# circuit_R2a.net
KiCad netlist of a schematic drawn in EAGLE
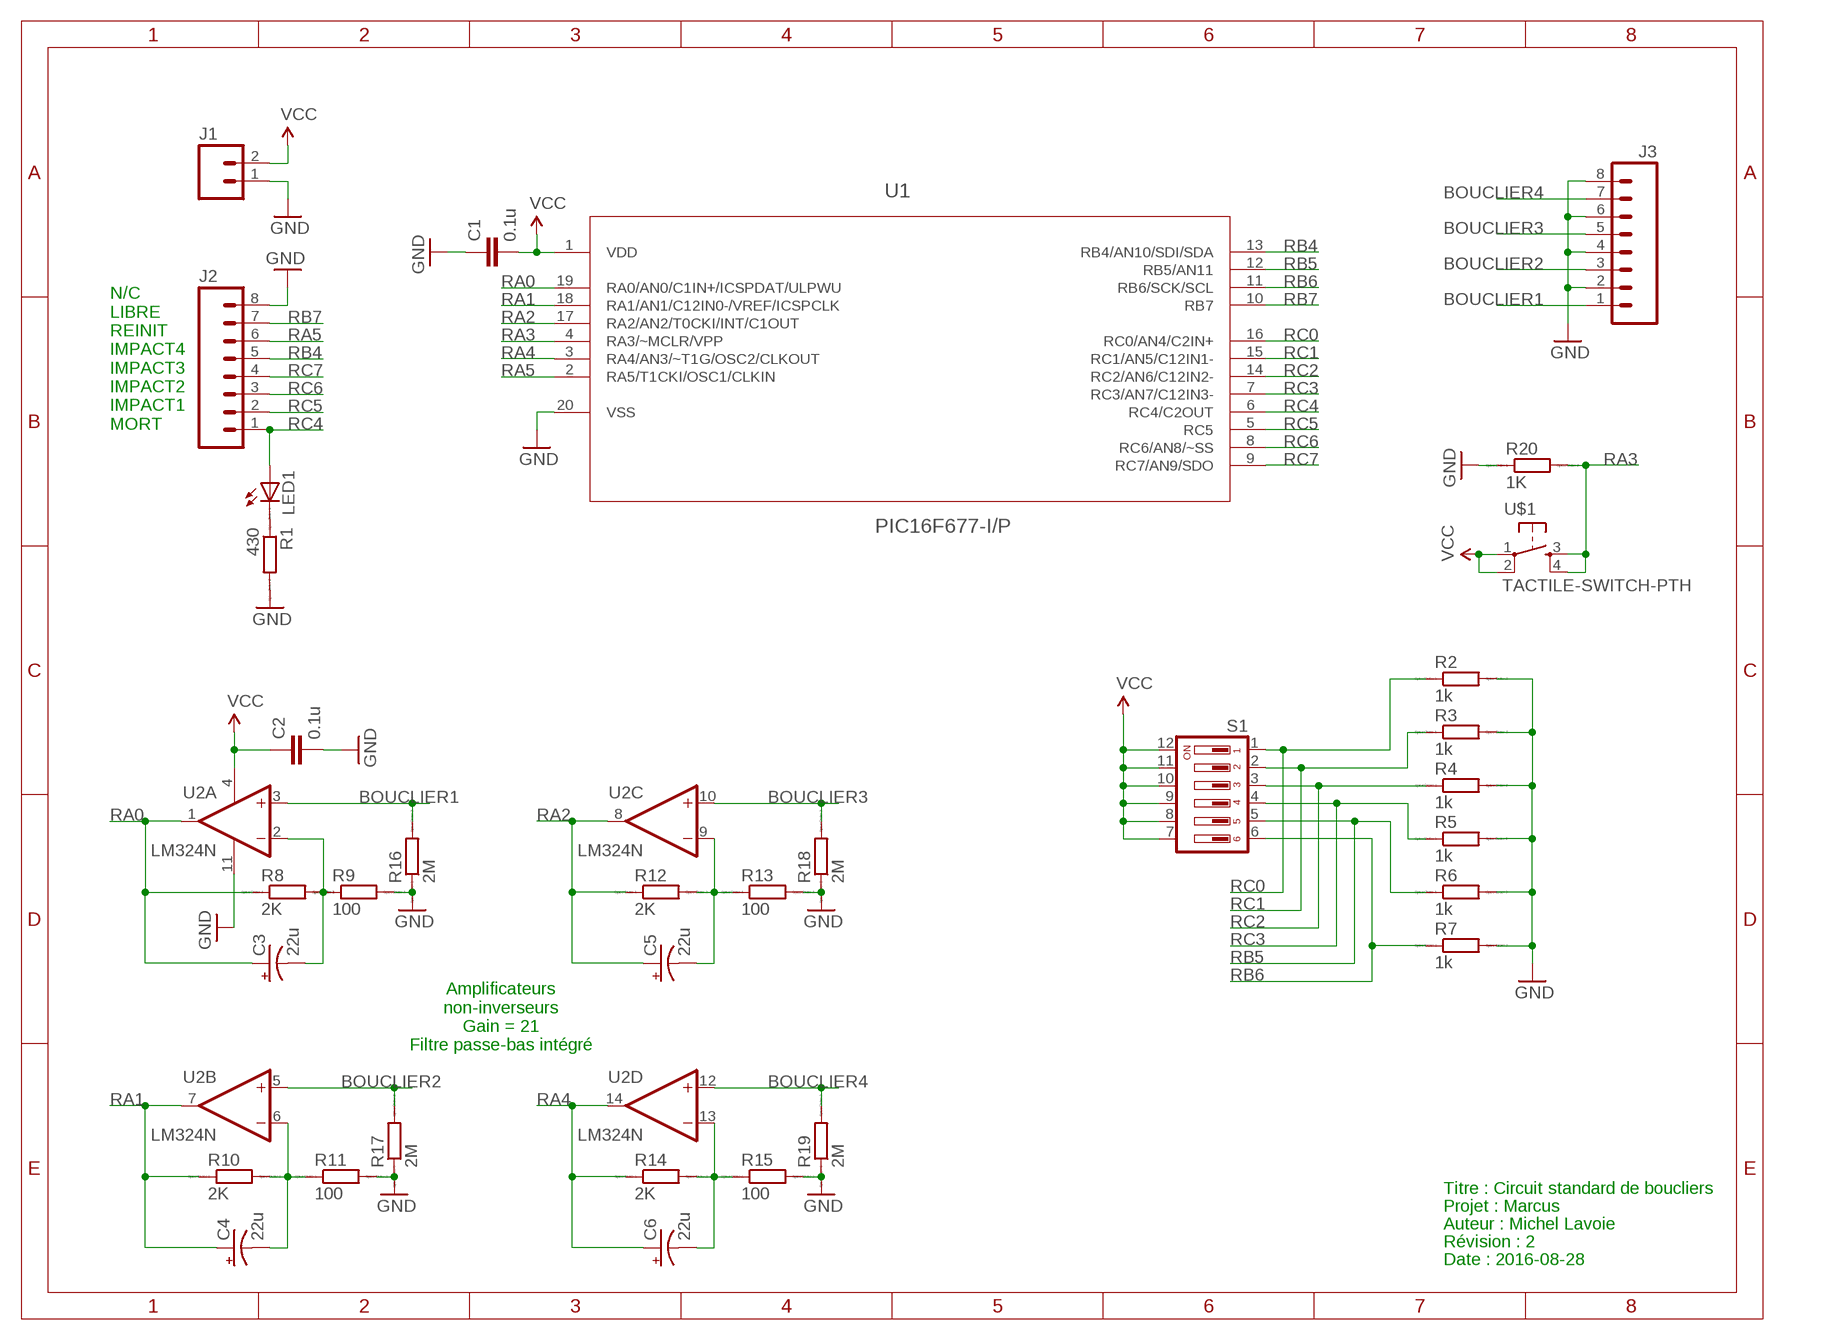
[diagram p0: schematic, sheet 1]

(export (version "E")
  (design (tool "Eeschema 10.0.6"))
  (components
    (comp (ref "C1")
      (value "0.1u")
      (footprint "eagle-import:CAP-PTH-SMALL")
      (libsource (lib "eagle-import") (part "CAPPTH"))
    )
    (comp (ref "C2")
      (value "0.1u")
      (footprint "eagle-import:CAP-PTH-SMALL")
      (libsource (lib "eagle-import") (part "CAPPTH"))
    )
    (comp (ref "C3")
      (value "22u")
      (footprint "eagle-import:E2,5-5")
      (libsource (lib "eagle-import") (part "CPOL-USE2.5-5"))
    )
    (comp (ref "C4")
      (value "22u")
      (footprint "eagle-import:E2,5-5")
      (libsource (lib "eagle-import") (part "CPOL-USE2.5-5"))
    )
    (comp (ref "C5")
      (value "22u")
      (footprint "eagle-import:E2,5-5")
      (libsource (lib "eagle-import") (part "CPOL-USE2.5-5"))
    )
    (comp (ref "C6")
      (value "22u")
      (footprint "eagle-import:E2,5-5")
      (libsource (lib "eagle-import") (part "CPOL-USE2.5-5"))
    )
    (comp (ref "J1")
      (value "M02PTH")
      (footprint "eagle-import:1X02")
      (libsource (lib "eagle-import") (part "M02PTH"))
    )
    (comp (ref "J2")
      (value "M08NO_SILK")
      (footprint "eagle-import:1X08_PIN1_NO_SILK")
      (libsource (lib "eagle-import") (part "M08NO_SILK"))
    )
    (comp (ref "J3")
      (value "M08NO_SILK")
      (footprint "eagle-import:1X08_PIN1_NO_SILK")
      (libsource (lib "eagle-import") (part "M08NO_SILK"))
    )
    (comp (ref "LED1")
      (value "LED3MM")
      (footprint "eagle-import:LED3MM")
      (libsource (lib "eagle-import") (part "LED3MM"))
    )
    (comp (ref "R1")
      (value "430")
      (footprint "eagle-import:0207_10")
      (libsource (lib "eagle-import") (part "R0207/10"))
    )
    (comp (ref "R2")
      (value "1k")
      (footprint "eagle-import:0207_10")
      (libsource (lib "eagle-import") (part "R0207/10"))
    )
    (comp (ref "R3")
      (value "1k")
      (footprint "eagle-import:0207_10")
      (libsource (lib "eagle-import") (part "R0207/10"))
    )
    (comp (ref "R4")
      (value "1k")
      (footprint "eagle-import:0207_10")
      (libsource (lib "eagle-import") (part "R0207/10"))
    )
    (comp (ref "R5")
      (value "1k")
      (footprint "eagle-import:0207_10")
      (libsource (lib "eagle-import") (part "R0207/10"))
    )
    (comp (ref "R6")
      (value "1k")
      (footprint "eagle-import:0207_10")
      (libsource (lib "eagle-import") (part "R0207/10"))
    )
    (comp (ref "R7")
      (value "1k")
      (footprint "eagle-import:0207_10")
      (libsource (lib "eagle-import") (part "R0207/10"))
    )
    (comp (ref "R8")
      (value "2K")
      (footprint "eagle-import:0207_10")
      (libsource (lib "eagle-import") (part "R0207/10"))
    )
    (comp (ref "R9")
      (value "100")
      (footprint "eagle-import:0207_10")
      (libsource (lib "eagle-import") (part "R0207/10"))
    )
    (comp (ref "R10")
      (value "2K")
      (footprint "eagle-import:0207_10")
      (libsource (lib "eagle-import") (part "R0207/10"))
    )
    (comp (ref "R11")
      (value "100")
      (footprint "eagle-import:0207_10")
      (libsource (lib "eagle-import") (part "R0207/10"))
    )
    (comp (ref "R12")
      (value "2K")
      (footprint "eagle-import:0207_10")
      (libsource (lib "eagle-import") (part "R0207/10"))
    )
    (comp (ref "R13")
      (value "100")
      (footprint "eagle-import:0207_10")
      (libsource (lib "eagle-import") (part "R0207/10"))
    )
    (comp (ref "R14")
      (value "2K")
      (footprint "eagle-import:0207_10")
      (libsource (lib "eagle-import") (part "R0207/10"))
    )
    (comp (ref "R15")
      (value "100")
      (footprint "eagle-import:0207_10")
      (libsource (lib "eagle-import") (part "R0207/10"))
    )
    (comp (ref "R16")
      (value "2M")
      (footprint "eagle-import:0207_10")
      (libsource (lib "eagle-import") (part "R0207/10"))
    )
    (comp (ref "R17")
      (value "2M")
      (footprint "eagle-import:0207_10")
      (libsource (lib "eagle-import") (part "R0207/10"))
    )
    (comp (ref "R18")
      (value "2M")
      (footprint "eagle-import:0207_10")
      (libsource (lib "eagle-import") (part "R0207/10"))
    )
    (comp (ref "R19")
      (value "2M")
      (footprint "eagle-import:0207_10")
      (libsource (lib "eagle-import") (part "R0207/10"))
    )
    (comp (ref "R20")
      (value "1K")
      (footprint "eagle-import:0207_10")
      (libsource (lib "eagle-import") (part "R0207/10"))
    )
    (comp (ref "S1")
      (value "DIP06YL")
      (footprint "eagle-import:DIP06YL")
      (libsource (lib "eagle-import") (part "DIP06YL"))
    )
    (comp (ref "U$1")
      (value "TACTILE-SWITCH-PTH")
      (footprint "eagle-import:TAC-SWITCH-PTH")
      (libsource (lib "eagle-import") (part "TACTILE-SWITCH-PTH"))
    )
    (comp (ref "U1")
      (value "PIC16F677-I/P")
      (footprint "eagle-import:DIP254P762X533-20")
      (libsource (lib "eagle-import") (part "PIC16F677-I/P"))
    )
    (comp (ref "U2")
      (value "LM324N")
      (footprint "eagle-import:DIL14")
      (libsource (lib "eagle-import") (part "LM324N"))
    )
  )
  (nets
    (net (code "1") (name "/BOUCLIER1") (class "Default")
      (node (ref "J3") (pin "1") (pinfunction "1_1") (pintype "passive"))
      (node (ref "R16") (pin "2") (pinfunction "2_2") (pintype "passive"))
      (node (ref "U2") (pin "3") (pinfunction "+IN_3") (pintype "input"))
    )
    (net (code "2") (name "/BOUCLIER2") (class "Default")
      (node (ref "J3") (pin "3") (pinfunction "3_3") (pintype "passive"))
      (node (ref "R17") (pin "2") (pinfunction "2_2") (pintype "passive"))
      (node (ref "U2") (pin "5") (pinfunction "+IN_5") (pintype "input"))
    )
    (net (code "3") (name "/BOUCLIER3") (class "Default")
      (node (ref "J3") (pin "5") (pinfunction "5_5") (pintype "passive"))
      (node (ref "R18") (pin "2") (pinfunction "2_2") (pintype "passive"))
      (node (ref "U2") (pin "10") (pinfunction "+IN_10") (pintype "input"))
    )
    (net (code "4") (name "/BOUCLIER4") (class "Default")
      (node (ref "J3") (pin "7") (pinfunction "7_7") (pintype "passive"))
      (node (ref "R19") (pin "2") (pinfunction "2_2") (pintype "passive"))
      (node (ref "U2") (pin "12") (pinfunction "+IN_12") (pintype "input"))
    )
    (net (code "5") (name "/RA0") (class "Default")
      (node (ref "C3") (pin "+") (pinfunction "+_+") (pintype "passive"))
      (node (ref "R8") (pin "1") (pinfunction "1_1") (pintype "passive"))
      (node (ref "U1") (pin "19") (pinfunction "RA0/AN0/C1IN+/ICSPDAT/ULPWU_19") (pintype "bidirectional"))
      (node (ref "U2") (pin "1") (pinfunction "OUT_1") (pintype "output"))
    )
    (net (code "6") (name "/RA1") (class "Default")
      (node (ref "C4") (pin "+") (pinfunction "+_+") (pintype "passive"))
      (node (ref "R10") (pin "1") (pinfunction "1_1") (pintype "passive"))
      (node (ref "U1") (pin "18") (pinfunction "RA1/AN1/C12IN0-/VREF/ICSPCLK_18") (pintype "bidirectional"))
      (node (ref "U2") (pin "7") (pinfunction "OUT_7") (pintype "output"))
    )
    (net (code "7") (name "/RA2") (class "Default")
      (node (ref "C5") (pin "+") (pinfunction "+_+") (pintype "passive"))
      (node (ref "R12") (pin "1") (pinfunction "1_1") (pintype "passive"))
      (node (ref "U1") (pin "17") (pinfunction "RA2/AN2/T0CKI/INT/C1OUT_17") (pintype "bidirectional"))
      (node (ref "U2") (pin "8") (pinfunction "OUT_8") (pintype "output"))
    )
    (net (code "8") (name "/RA3") (class "Default")
      (node (ref "R20") (pin "2") (pinfunction "2_2") (pintype "passive"))
      (node (ref "U$1") (pin "3") (pinfunction "3_3") (pintype "passive"))
      (node (ref "U$1") (pin "4") (pinfunction "4_4") (pintype "passive"))
      (node (ref "U1") (pin "4") (pinfunction "RA3/~{MCLR/VPP}_4") (pintype "bidirectional"))
    )
    (net (code "9") (name "/RA4") (class "Default")
      (node (ref "C6") (pin "+") (pinfunction "+_+") (pintype "passive"))
      (node (ref "R14") (pin "1") (pinfunction "1_1") (pintype "passive"))
      (node (ref "U1") (pin "3") (pinfunction "RA4/AN3/~{T1G/OSC2/CLKOUT}_3") (pintype "bidirectional"))
      (node (ref "U2") (pin "14") (pinfunction "OUT_14") (pintype "output"))
    )
    (net (code "10") (name "/RA5") (class "Default")
      (node (ref "J2") (pin "6") (pinfunction "6_6") (pintype "passive"))
      (node (ref "U1") (pin "2") (pinfunction "RA5/T1CKI/OSC1/CLKIN_2") (pintype "bidirectional"))
    )
    (net (code "11") (name "/RB4") (class "Default")
      (node (ref "J2") (pin "5") (pinfunction "5_5") (pintype "passive"))
      (node (ref "U1") (pin "13") (pinfunction "RB4/AN10/SDI/SDA_13") (pintype "bidirectional"))
    )
    (net (code "12") (name "/RB5") (class "Default")
      (node (ref "R6") (pin "1") (pinfunction "1_1") (pintype "passive"))
      (node (ref "S1") (pin "5") (pinfunction "5_5") (pintype "passive"))
      (node (ref "U1") (pin "12") (pinfunction "RB5/AN11_12") (pintype "bidirectional"))
    )
    (net (code "13") (name "/RB6") (class "Default")
      (node (ref "R7") (pin "1") (pinfunction "1_1") (pintype "passive"))
      (node (ref "S1") (pin "6") (pinfunction "6_6") (pintype "passive"))
      (node (ref "U1") (pin "11") (pinfunction "RB6/SCK/SCL_11") (pintype "bidirectional"))
    )
    (net (code "14") (name "/RB7") (class "Default")
      (node (ref "J2") (pin "7") (pinfunction "7_7") (pintype "passive"))
      (node (ref "U1") (pin "10") (pinfunction "RB7_10") (pintype "bidirectional"))
    )
    (net (code "15") (name "/RC0") (class "Default")
      (node (ref "R2") (pin "1") (pinfunction "1_1") (pintype "passive"))
      (node (ref "S1") (pin "1") (pinfunction "1_1") (pintype "passive"))
      (node (ref "U1") (pin "16") (pinfunction "RC0/AN4/C2IN+_16") (pintype "bidirectional"))
    )
    (net (code "16") (name "/RC1") (class "Default")
      (node (ref "R3") (pin "1") (pinfunction "1_1") (pintype "passive"))
      (node (ref "S1") (pin "2") (pinfunction "2_2") (pintype "passive"))
      (node (ref "U1") (pin "15") (pinfunction "RC1/AN5/C12IN1-_15") (pintype "bidirectional"))
    )
    (net (code "17") (name "/RC2") (class "Default")
      (node (ref "R4") (pin "1") (pinfunction "1_1") (pintype "passive"))
      (node (ref "S1") (pin "3") (pinfunction "3_3") (pintype "passive"))
      (node (ref "U1") (pin "14") (pinfunction "RC2/AN6/C12IN2-_14") (pintype "bidirectional"))
    )
    (net (code "18") (name "/RC3") (class "Default")
      (node (ref "R5") (pin "1") (pinfunction "1_1") (pintype "passive"))
      (node (ref "S1") (pin "4") (pinfunction "4_4") (pintype "passive"))
      (node (ref "U1") (pin "7") (pinfunction "RC3/AN7/C12IN3-_7") (pintype "bidirectional"))
    )
    (net (code "19") (name "/RC4") (class "Default")
      (node (ref "J2") (pin "1") (pinfunction "1_1") (pintype "passive"))
      (node (ref "LED1") (pin "A") (pinfunction "A_A") (pintype "passive"))
      (node (ref "U1") (pin "6") (pinfunction "RC4/C2OUT_6") (pintype "bidirectional"))
    )
    (net (code "20") (name "/RC5") (class "Default")
      (node (ref "J2") (pin "2") (pinfunction "2_2") (pintype "passive"))
      (node (ref "U1") (pin "5") (pinfunction "RC5_5") (pintype "bidirectional"))
    )
    (net (code "21") (name "/RC6") (class "Default")
      (node (ref "J2") (pin "3") (pinfunction "3_3") (pintype "passive"))
      (node (ref "U1") (pin "8") (pinfunction "RC6/AN8/~{SS}_8") (pintype "bidirectional"))
    )
    (net (code "22") (name "/RC7") (class "Default")
      (node (ref "J2") (pin "4") (pinfunction "4_4") (pintype "passive"))
      (node (ref "U1") (pin "9") (pinfunction "RC7/AN9/SDO_9") (pintype "bidirectional"))
    )
    (net (code "23") (name "GND") (class "Default")
      (node (ref "C1") (pin "1") (pinfunction "1_1") (pintype "passive"))
      (node (ref "C2") (pin "2") (pinfunction "2_2") (pintype "passive"))
      (node (ref "J1") (pin "1") (pinfunction "1_1") (pintype "passive"))
      (node (ref "J2") (pin "8") (pinfunction "8_8") (pintype "passive"))
      (node (ref "J3") (pin "2") (pinfunction "2_2") (pintype "passive"))
      (node (ref "J3") (pin "4") (pinfunction "4_4") (pintype "passive"))
      (node (ref "J3") (pin "6") (pinfunction "6_6") (pintype "passive"))
      (node (ref "J3") (pin "8") (pinfunction "8_8") (pintype "passive"))
      (node (ref "R1") (pin "2") (pinfunction "2_2") (pintype "passive"))
      (node (ref "R11") (pin "2") (pinfunction "2_2") (pintype "passive"))
      (node (ref "R13") (pin "2") (pinfunction "2_2") (pintype "passive"))
      (node (ref "R15") (pin "2") (pinfunction "2_2") (pintype "passive"))
      (node (ref "R16") (pin "1") (pinfunction "1_1") (pintype "passive"))
      (node (ref "R17") (pin "1") (pinfunction "1_1") (pintype "passive"))
      (node (ref "R18") (pin "1") (pinfunction "1_1") (pintype "passive"))
      (node (ref "R19") (pin "1") (pinfunction "1_1") (pintype "passive"))
      (node (ref "R2") (pin "2") (pinfunction "2_2") (pintype "passive"))
      (node (ref "R20") (pin "1") (pinfunction "1_1") (pintype "passive"))
      (node (ref "R3") (pin "2") (pinfunction "2_2") (pintype "passive"))
      (node (ref "R4") (pin "2") (pinfunction "2_2") (pintype "passive"))
      (node (ref "R5") (pin "2") (pinfunction "2_2") (pintype "passive"))
      (node (ref "R6") (pin "2") (pinfunction "2_2") (pintype "passive"))
      (node (ref "R7") (pin "2") (pinfunction "2_2") (pintype "passive"))
      (node (ref "R9") (pin "2") (pinfunction "2_2") (pintype "passive"))
      (node (ref "U1") (pin "20") (pinfunction "VSS_20") (pintype "power_in"))
      (node (ref "U2") (pin "11") (pinfunction "V-_11") (pintype "power_in"))
    )
    (net (code "24") (name "Net-(LED1-C)") (class "Default")
      (node (ref "LED1") (pin "K") (pinfunction "C_K") (pintype "passive"))
      (node (ref "R1") (pin "1") (pinfunction "1_1") (pintype "passive"))
    )
    (net (code "25") (name "Net-(U2A--IN)") (class "Default")
      (node (ref "C3") (pin "-") (pinfunction "-_-") (pintype "passive"))
      (node (ref "R8") (pin "2") (pinfunction "2_2") (pintype "passive"))
      (node (ref "R9") (pin "1") (pinfunction "1_1") (pintype "passive"))
      (node (ref "U2") (pin "2") (pinfunction "-IN_2") (pintype "input"))
    )
    (net (code "26") (name "Net-(U2B--IN)") (class "Default")
      (node (ref "C4") (pin "-") (pinfunction "-_-") (pintype "passive"))
      (node (ref "R10") (pin "2") (pinfunction "2_2") (pintype "passive"))
      (node (ref "R11") (pin "1") (pinfunction "1_1") (pintype "passive"))
      (node (ref "U2") (pin "6") (pinfunction "-IN_6") (pintype "input"))
    )
    (net (code "27") (name "Net-(U2C--IN)") (class "Default")
      (node (ref "C5") (pin "-") (pinfunction "-_-") (pintype "passive"))
      (node (ref "R12") (pin "2") (pinfunction "2_2") (pintype "passive"))
      (node (ref "R13") (pin "1") (pinfunction "1_1") (pintype "passive"))
      (node (ref "U2") (pin "9") (pinfunction "-IN_9") (pintype "input"))
    )
    (net (code "28") (name "Net-(U2D--IN)") (class "Default")
      (node (ref "C6") (pin "-") (pinfunction "-_-") (pintype "passive"))
      (node (ref "R14") (pin "2") (pinfunction "2_2") (pintype "passive"))
      (node (ref "R15") (pin "1") (pinfunction "1_1") (pintype "passive"))
      (node (ref "U2") (pin "13") (pinfunction "-IN_13") (pintype "input"))
    )
    (net (code "29") (name "VCC") (class "Default")
      (node (ref "C1") (pin "2") (pinfunction "2_2") (pintype "passive"))
      (node (ref "C2") (pin "1") (pinfunction "1_1") (pintype "passive"))
      (node (ref "J1") (pin "2") (pinfunction "2_2") (pintype "passive"))
      (node (ref "S1") (pin "10") (pinfunction "10_10") (pintype "passive"))
      (node (ref "S1") (pin "11") (pinfunction "11_11") (pintype "passive"))
      (node (ref "S1") (pin "12") (pinfunction "12_12") (pintype "passive"))
      (node (ref "S1") (pin "7") (pinfunction "7_7") (pintype "passive"))
      (node (ref "S1") (pin "8") (pinfunction "8_8") (pintype "passive"))
      (node (ref "S1") (pin "9") (pinfunction "9_9") (pintype "passive"))
      (node (ref "U$1") (pin "1") (pinfunction "1_1") (pintype "passive"))
      (node (ref "U$1") (pin "2") (pinfunction "2_2") (pintype "passive"))
      (node (ref "U1") (pin "1") (pinfunction "VDD_1") (pintype "power_in"))
      (node (ref "U2") (pin "4") (pinfunction "V+_4") (pintype "power_in"))
    )
  )
)
